# final.net
KiCad netlist of a schematic drawn in EAGLE
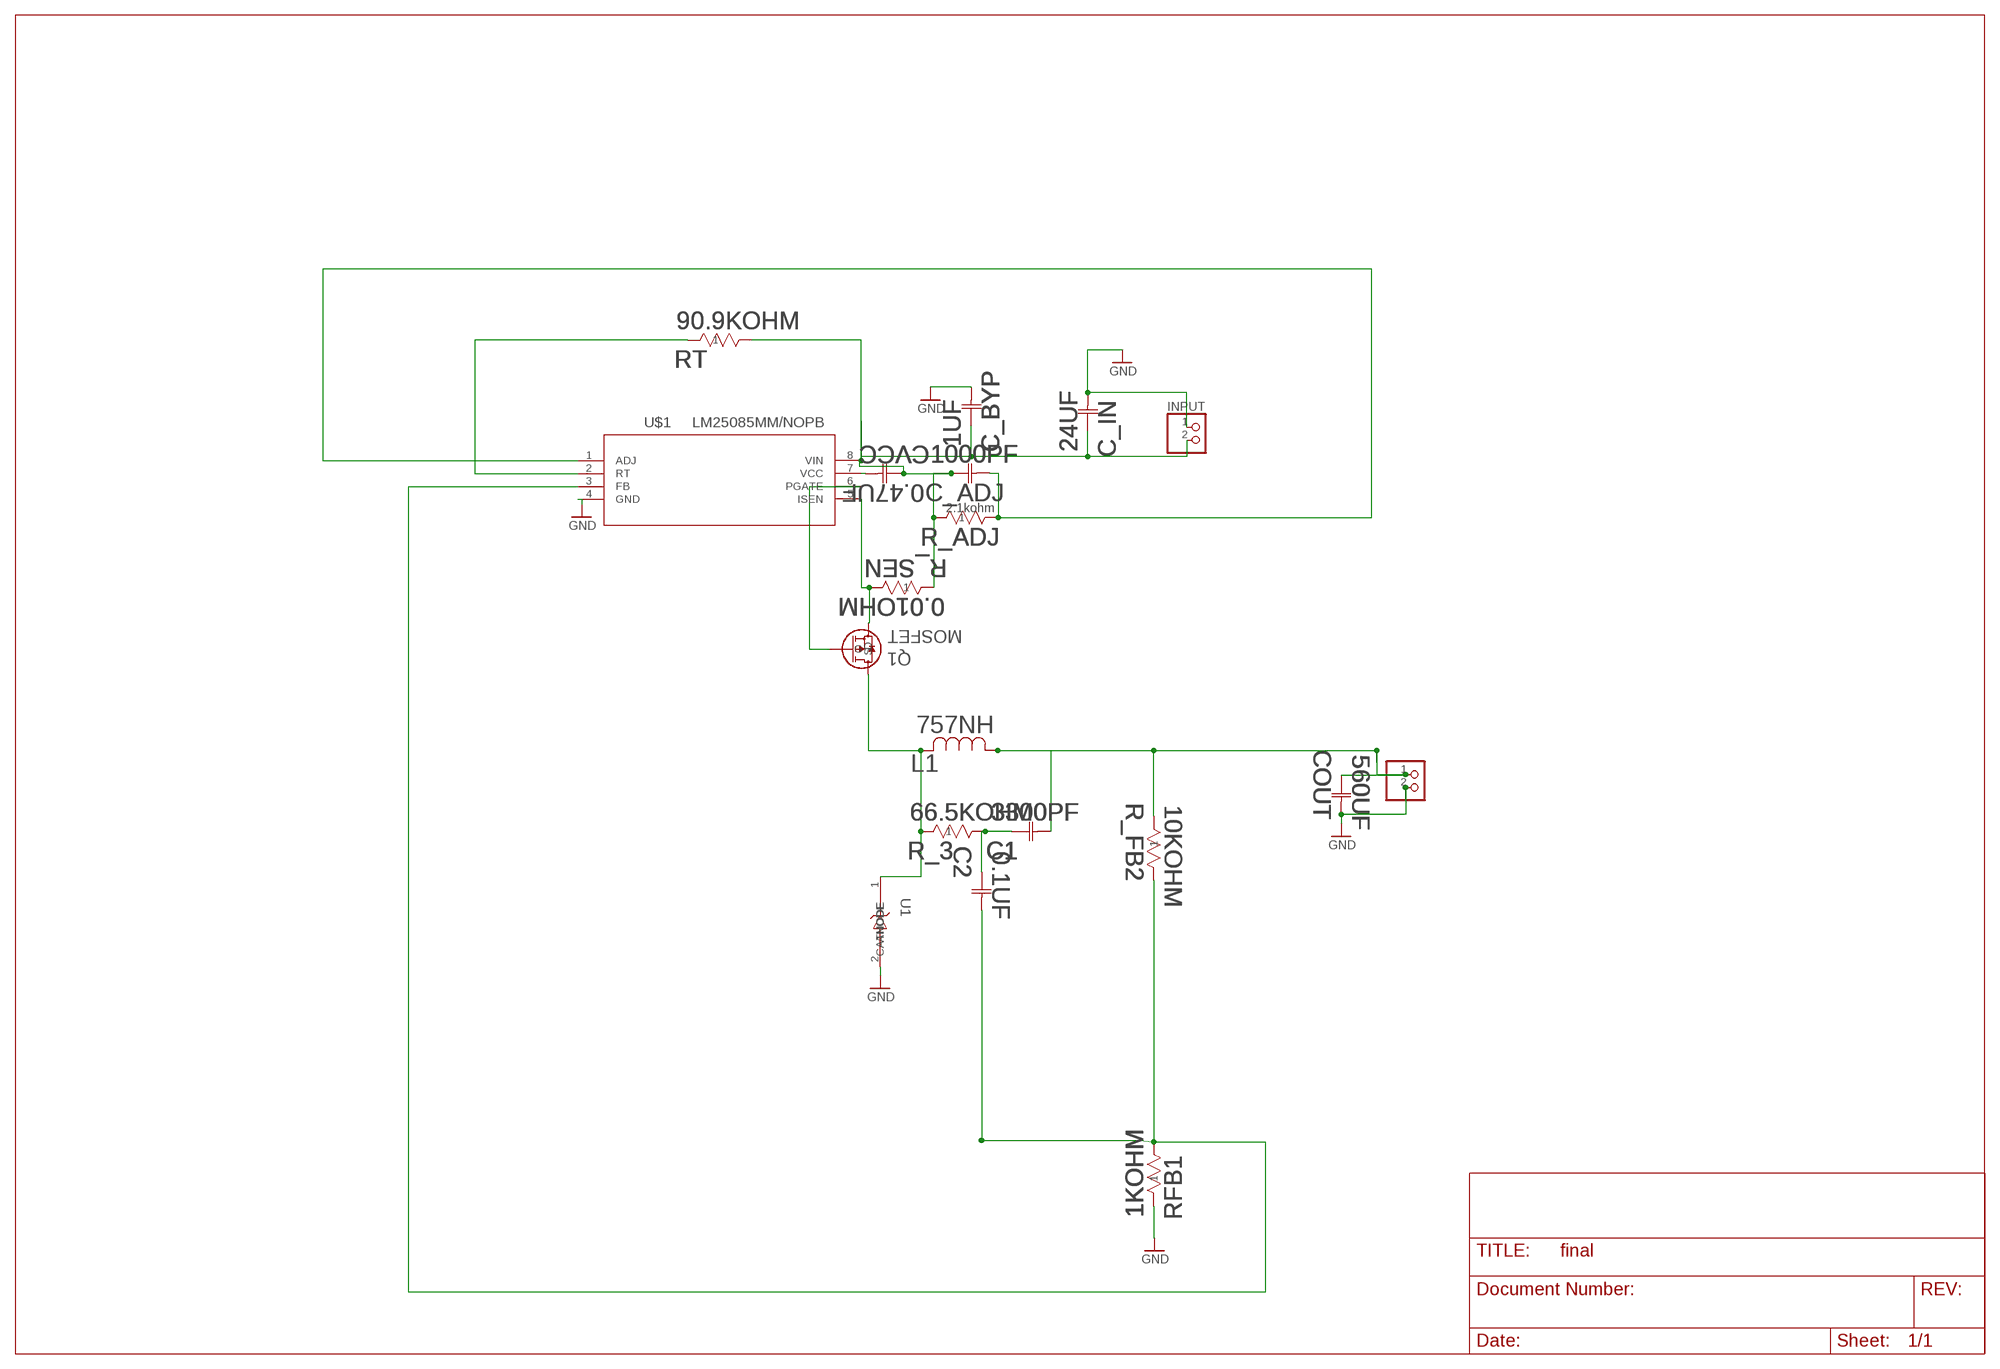
[diagram p0: schematic, sheet 1]

(export (version "E")
  (design (tool "Eeschema 10.0.6"))
  (components
    (comp (ref "0.01OHM")
      (value "R_SEN")
      (footprint "eagle-import:STA_MPR5_STP")
      (fields
        (field (name "MANUFACTURER_PART_NUMBER") "MPR5JB10L0")
        (field (name "COPYRIGHT") "Copyright (C) 2023 Ultra Librarian. All rights reserved.")
      )
      (libsource (lib "eagle-import") (part "R_SEN"))
    )
    (comp (ref "0.1UF")
      (value "C2")
      (footprint "eagle-import:U2-D_NCH")
      (fields
        (field (name "MANUFACTURER_PART_NUMBER") "UCB1V0R1MCL1GS")
        (field (name "COPYRIGHT") "Copyright (C) 2023 Ultra Librarian. All rights reserved.")
      )
      (libsource (lib "eagle-import") (part "C2"))
    )
    (comp (ref "0.47UF")
      (value "CVCC")
      (footprint "eagle-import:CAP_WCAP-ATG8_05.0X11.0_WRE")
      (fields
        (field (name "MANUFACTURER_PART_NUMBER") "860010672004")
        (field (name "COPYRIGHT") "Copyright (C) 2023 Ultra Librarian. All rights reserved.")
      )
      (libsource (lib "eagle-import") (part "CVCC"))
    )
    (comp (ref "1KOHM")
      (value "RFB1")
      (footprint "eagle-import:STA_CF14_STP")
      (fields
        (field (name "MANUFACTURER_PART_NUMBER") "CF14JT1K00")
        (field (name "COPYRIGHT") "Copyright (C) 2023 Ultra Librarian. All rights reserved.")
      )
      (libsource (lib "eagle-import") (part "RFB1"))
    )
    (comp (ref "1UF")
      (value "C_BYP")
      (footprint "eagle-import:CAP_FG26_TDK")
      (fields
        (field (name "MANUFACTURER_PART_NUMBER") "FG26X7R1E105KNT06")
        (field (name "COPYRIGHT") "Copyright (C) 2023 Ultra Librarian. All rights reserved.")
      )
      (libsource (lib "eagle-import") (part "C_BYP"))
    )
    (comp (ref "2.1KOHM")
      (value "R_ADJ")
      (footprint "eagle-import:STA_RNF14_STP")
      (fields
        (field (name "MANUFACTURER_PART_NUMBER") "RNF14FTD3K40")
        (field (name "COPYRIGHT") "Copyright (C) 2023 Ultra Librarian. All rights reserved.")
      )
      (libsource (lib "eagle-import") (part "R_ADJ"))
    )
    (comp (ref "10KOHM")
      (value "R_FB2")
      (footprint "eagle-import:STA_CF14_STP")
      (fields
        (field (name "MANUFACTURER_PART_NUMBER") "CF14JT10K0")
        (field (name "COPYRIGHT") "Copyright (C) 2023 Ultra Librarian. All rights reserved.")
      )
      (libsource (lib "eagle-import") (part "R_FB2"))
    )
    (comp (ref "24UF")
      (value "C_IN")
      (footprint "eagle-import:CAP_5X11_WRE")
      (fields
        (field (name "MANUFACTURER_PART_NUMBER") "860160472004")
        (field (name "COPYRIGHT") "Copyright (C) 2023 Ultra Librarian. All rights reserved.")
      )
      (libsource (lib "eagle-import") (part "C_IN"))
    )
    (comp (ref "66.5KOHM")
      (value "R_3")
      (footprint "eagle-import:RES_CMF50_VIS")
      (fields
        (field (name "MANUFACTURER_PART_NUMBER") "CMF5066R500FHEB")
        (field (name "COPYRIGHT") "Copyright (C) 2023 Ultra Librarian. All rights reserved.")
      )
      (libsource (lib "eagle-import") (part "R_3"))
    )
    (comp (ref "90.9KOHM")
      (value "RT")
      (footprint "eagle-import:YAG_MF25_YAG")
      (fields
        (field (name "MANUFACTURER_PART_NUMBER") "MFR-25FBF52-90K9")
        (field (name "COPYRIGHT") "Copyright (C) 2023 Ultra Librarian. All rights reserved.")
      )
      (libsource (lib "eagle-import") (part "RT"))
    )
    (comp (ref "560UF")
      (value "COUT")
      (footprint "eagle-import:CAP_PAN_10X20_PAN")
      (fields
        (field (name "MANUFACTURER_PART_NUMBER") "EEUFR1V561B")
        (field (name "COPYRIGHT") "Copyright (C) 2023 Ultra Librarian. All rights reserved.")
      )
      (libsource (lib "eagle-import") (part "COUT"))
    )
    (comp (ref "757NH")
      (value "L1")
      (footprint "eagle-import:IND_TAIYO_NRS6020_TAY")
      (fields
        (field (name "MANUFACTURER_PART_NUMBER") "NRS6020T0R8NMGG")
        (field (name "COPYRIGHT") "Copyright (C) 2023 Ultra Librarian. All rights reserved.")
      )
      (libsource (lib "eagle-import") (part "L1"))
    )
    (comp (ref "1000PF")
      (value "C_ADJ")
      (footprint "eagle-import:CAP_VY1_Y5U_9X5X13-10_VIS")
      (fields
        (field (name "MANUFACTURER_PART_NUMBER") "VY1102M31Y5UC63V0")
        (field (name "COPYRIGHT") "Copyright (C) 2023 Ultra Librarian. All rights reserved.")
      )
      (libsource (lib "eagle-import") (part "C_ADJ"))
    )
    (comp (ref "3300PF")
      (value "C1")
      (footprint "eagle-import:G-21_MUR")
      (fields
        (field (name "MANUFACTURER_PART_NUMBER") "GRM2165C1H332JA01D")
        (field (name "COPYRIGHT") "Copyright (C) 2023 Ultra Librarian. All rights reserved.")
      )
      (libsource (lib "eagle-import") (part "C1"))
    )
    (comp (ref "INPUT")
      (value "PINHD-1X2")
      (footprint "eagle-import:1X02")
      (libsource (lib "eagle-import") (part "PINHD-1X2"))
    )
    (comp (ref "OUTPUT")
      (value "PINHD-1X2")
      (footprint "eagle-import:1X02")
      (libsource (lib "eagle-import") (part "PINHD-1X2"))
    )
    (comp (ref "Q1")
      (value "MOSFET")
      (footprint "eagle-import:SOT-23_DMP2123L_DIO")
      (fields
        (field (name "MANUFACTURER_PART_NUMBER") "DMP2123L-7")
        (field (name "COPYRIGHT") "Copyright (C) 2023 Ultra Librarian. All rights reserved.")
      )
      (libsource (lib "eagle-import") (part "MOSFET"))
    )
    (comp (ref "U$1")
      (value "LM25085MM/NOPB")
      (footprint "eagle-import:MUA08A")
      (fields (field (name "COPYRIGHT") "Copyright (C) 2023 Ultra Librarian. All rights reserved."))
      (libsource (lib "eagle-import") (part "LM25085MM/NOPB"))
    )
    (comp (ref "U1")
      (value "DIODE")
      (footprint "eagle-import:CASE_267-05_ONS")
      (fields
        (field (name "MANUFACTURER_PART_NUMBER") "1N5406RLG")
        (field (name "COPYRIGHT") "Copyright (C) 2023 Ultra Librarian. All rights reserved.")
      )
      (libsource (lib "eagle-import") (part "DIODE"))
    )
  )
  (nets
    (net (code "1") (name "GND") (class "Default")
      (node (ref "1KOHM") (pin "1") (pinfunction "1_1") (pintype "passive"))
      (node (ref "1UF") (pin "2") (pinfunction "2_2") (pintype "passive"))
      (node (ref "24UF") (pin "2") (pinfunction "2_2") (pintype "passive"))
      (node (ref "560UF") (pin "2") (pinfunction "2_2") (pintype "passive"))
      (node (ref "INPUT") (pin "1") (pinfunction "1_1") (pintype "passive"))
      (node (ref "OUTPUT") (pin "2") (pinfunction "2_2") (pintype "passive"))
      (node (ref "U$1") (pin "4") (pinfunction "GND_4") (pintype "power_in"))
      (node (ref "U1") (pin "2") (pinfunction "ANODE_2") (pintype "passive"))
    )
    (net (code "2") (name "Net-(0.1UF-Pad1)") (class "Default")
      (node (ref "0.1UF") (pin "1") (pinfunction "1_1") (pintype "passive"))
      (node (ref "3300PF") (pin "1") (pinfunction "1_1") (pintype "passive"))
      (node (ref "66.5KOHM") (pin "2") (pinfunction "2_2") (pintype "passive"))
    )
    (net (code "3") (name "Net-(10KOHM-Pad1)") (class "Default")
      (node (ref "10KOHM") (pin "1") (pinfunction "1_1") (pintype "passive"))
      (node (ref "3300PF") (pin "2") (pinfunction "2_2") (pintype "passive"))
      (node (ref "560UF") (pin "1") (pinfunction "1_1") (pintype "passive"))
      (node (ref "757NH") (pin "1") (pinfunction "1_1") (pintype "passive"))
      (node (ref "OUTPUT") (pin "1") (pinfunction "1_1") (pintype "passive"))
    )
    (net (code "4") (name "Net-(Q1-D)") (class "Default")
      (node (ref "66.5KOHM") (pin "1") (pinfunction "1_1") (pintype "passive"))
      (node (ref "757NH") (pin "2") (pinfunction "2_2") (pintype "passive"))
      (node (ref "Q1") (pin "2") (pinfunction "D_2") (pintype "passive"))
      (node (ref "U1") (pin "1") (pinfunction "CATHODE_1") (pintype "passive"))
    )
    (net (code "5") (name "Net-(Q1-G)") (class "Default")
      (node (ref "Q1") (pin "1") (pinfunction "G_1") (pintype "passive"))
      (node (ref "U$1") (pin "6") (pinfunction "PGATE_6") (pintype "output"))
    )
    (net (code "6") (name "Net-(Q1-S)") (class "Default")
      (node (ref "0.01OHM") (pin "2") (pinfunction "2_2") (pintype "passive"))
      (node (ref "Q1") (pin "3") (pinfunction "S_3") (pintype "passive"))
      (node (ref "U$1") (pin "5") (pinfunction "ISEN_5") (pintype "input"))
    )
    (net (code "7") (name "Net-(U$1-ADJ)") (class "Default")
      (node (ref "1000PF") (pin "2") (pinfunction "2_2") (pintype "passive"))
      (node (ref "2.1KOHM") (pin "2") (pinfunction "2_2") (pintype "passive"))
      (node (ref "U$1") (pin "1") (pinfunction "ADJ_1") (pintype "input"))
    )
    (net (code "8") (name "Net-(U$1-FB)") (class "Default")
      (node (ref "0.1UF") (pin "2") (pinfunction "2_2") (pintype "passive"))
      (node (ref "10KOHM") (pin "2") (pinfunction "2_2") (pintype "passive"))
      (node (ref "1KOHM") (pin "2") (pinfunction "2_2") (pintype "passive"))
      (node (ref "U$1") (pin "3") (pinfunction "FB_3") (pintype "input"))
    )
    (net (code "9") (name "Net-(U$1-RT)") (class "Default")
      (node (ref "90.9KOHM") (pin "1") (pinfunction "1_1") (pintype "passive"))
      (node (ref "U$1") (pin "2") (pinfunction "RT_2") (pintype "input"))
    )
    (net (code "10") (name "Net-(U$1-VCC)") (class "Default")
      (node (ref "0.47UF") (pin "2") (pinfunction "2_2") (pintype "passive"))
      (node (ref "U$1") (pin "7") (pinfunction "VCC_7") (pintype "power_in"))
    )
    (net (code "11") (name "Net-(U$1-VIN)") (class "Default")
      (node (ref "0.01OHM") (pin "1") (pinfunction "1_1") (pintype "passive"))
      (node (ref "0.47UF") (pin "1") (pinfunction "1_1") (pintype "passive"))
      (node (ref "1000PF") (pin "1") (pinfunction "1_1") (pintype "passive"))
      (node (ref "1UF") (pin "1") (pinfunction "1_1") (pintype "passive"))
      (node (ref "2.1KOHM") (pin "1") (pinfunction "1_1") (pintype "passive"))
      (node (ref "24UF") (pin "1") (pinfunction "1_1") (pintype "passive"))
      (node (ref "90.9KOHM") (pin "2") (pinfunction "2_2") (pintype "passive"))
      (node (ref "INPUT") (pin "2") (pinfunction "2_2") (pintype "passive"))
      (node (ref "U$1") (pin "8") (pinfunction "VIN_8") (pintype "power_in"))
    )
  )
)
